# snes2p.net
KiCad netlist of a schematic drawn in EAGLE
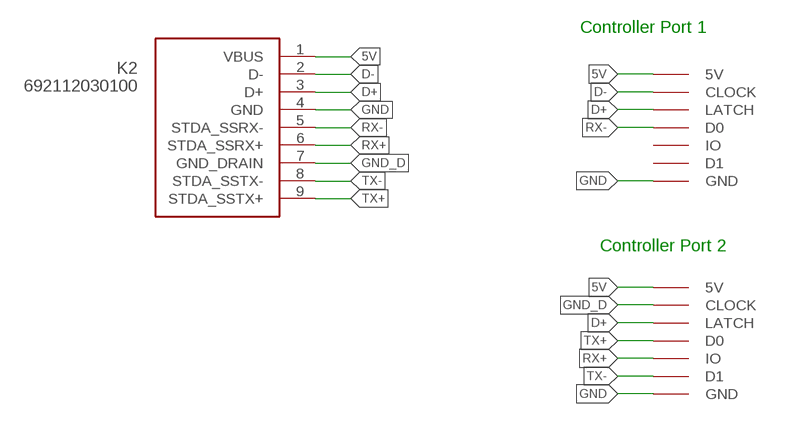
[diagram p0: schematic, sheet 1]

(export (version "E")
  (design (tool "Eeschema 10.0.6"))
  (components
    (comp (ref "K2")
      (value "692112030100")
      (footprint "eagle-import:692112030100")
      (libsource (lib "eagle-import") (part "692112030100"))
    )
    (comp (ref "U$1")
      (value "SNESCONN")
      (footprint "eagle-import:SNESCONN")
      (libsource (lib "eagle-import") (part "SNESCONN"))
    )
    (comp (ref "U$2")
      (value "SNESCONN")
      (footprint "eagle-import:SNESCONN")
      (libsource (lib "eagle-import") (part "SNESCONN"))
    )
  )
  (nets
    (net (code "1") (name "5V") (class "Default")
      (node (ref "K2") (pin "1") (pinfunction "VBUS_1") (pintype "bidirectional"))
      (node (ref "U$1") (pin "5V") (pinfunction "5V_5V") (pintype "input"))
      (node (ref "U$2") (pin "5V") (pinfunction "5V_5V") (pintype "input"))
    )
    (net (code "2") (name "D+") (class "Default")
      (node (ref "K2") (pin "3") (pinfunction "D+_3") (pintype "bidirectional"))
      (node (ref "U$1") (pin "LATCH") (pinfunction "LATCH_LATCH") (pintype "input"))
      (node (ref "U$2") (pin "LATCH") (pinfunction "LATCH_LATCH") (pintype "input"))
    )
    (net (code "3") (name "D-") (class "Default")
      (node (ref "K2") (pin "2") (pinfunction "D-_2") (pintype "bidirectional"))
      (node (ref "U$1") (pin "CLOCK") (pinfunction "CLOCK_CLOCK") (pintype "input"))
    )
    (net (code "4") (name "GND") (class "Default")
      (node (ref "K2") (pin "4") (pinfunction "GND_4") (pintype "bidirectional"))
      (node (ref "U$1") (pin "GND") (pinfunction "GND_GND") (pintype "power_in"))
      (node (ref "U$2") (pin "GND") (pinfunction "GND_GND") (pintype "power_in"))
    )
    (net (code "5") (name "GND_D") (class "Default")
      (node (ref "K2") (pin "7") (pinfunction "GND_DRAIN_7") (pintype "bidirectional"))
      (node (ref "U$2") (pin "CLOCK") (pinfunction "CLOCK_CLOCK") (pintype "input"))
    )
    (net (code "6") (name "RX+") (class "Default")
      (node (ref "K2") (pin "6") (pinfunction "STDA_SSRX+_6") (pintype "bidirectional"))
      (node (ref "U$2") (pin "IO") (pinfunction "IO_IO") (pintype "bidirectional"))
    )
    (net (code "7") (name "RX-") (class "Default")
      (node (ref "K2") (pin "5") (pinfunction "STDA_SSRX-_5") (pintype "bidirectional"))
      (node (ref "U$1") (pin "D0") (pinfunction "D0_D0") (pintype "bidirectional"))
    )
    (net (code "8") (name "TX+") (class "Default")
      (node (ref "K2") (pin "9") (pinfunction "STDA_SSTX+_9") (pintype "bidirectional"))
      (node (ref "U$2") (pin "D0") (pinfunction "D0_D0") (pintype "bidirectional"))
    )
    (net (code "9") (name "TX-") (class "Default")
      (node (ref "K2") (pin "8") (pinfunction "STDA_SSTX-_8") (pintype "bidirectional"))
      (node (ref "U$2") (pin "D1") (pinfunction "D1_D1") (pintype "bidirectional"))
    )
    (net (code "10") (name "unconnected-(U$1-PadD1)") (class "Default")
      (node (ref "U$1") (pin "D1") (pinfunction "D1_D1") (pintype "bidirectional"))
    )
    (net (code "11") (name "unconnected-(U$1-PadIO)") (class "Default")
      (node (ref "U$1") (pin "IO") (pinfunction "IO_IO") (pintype "bidirectional"))
    )
  )
)
